# Automaton_no_switches.net
KiCad netlist of a schematic drawn in EAGLE
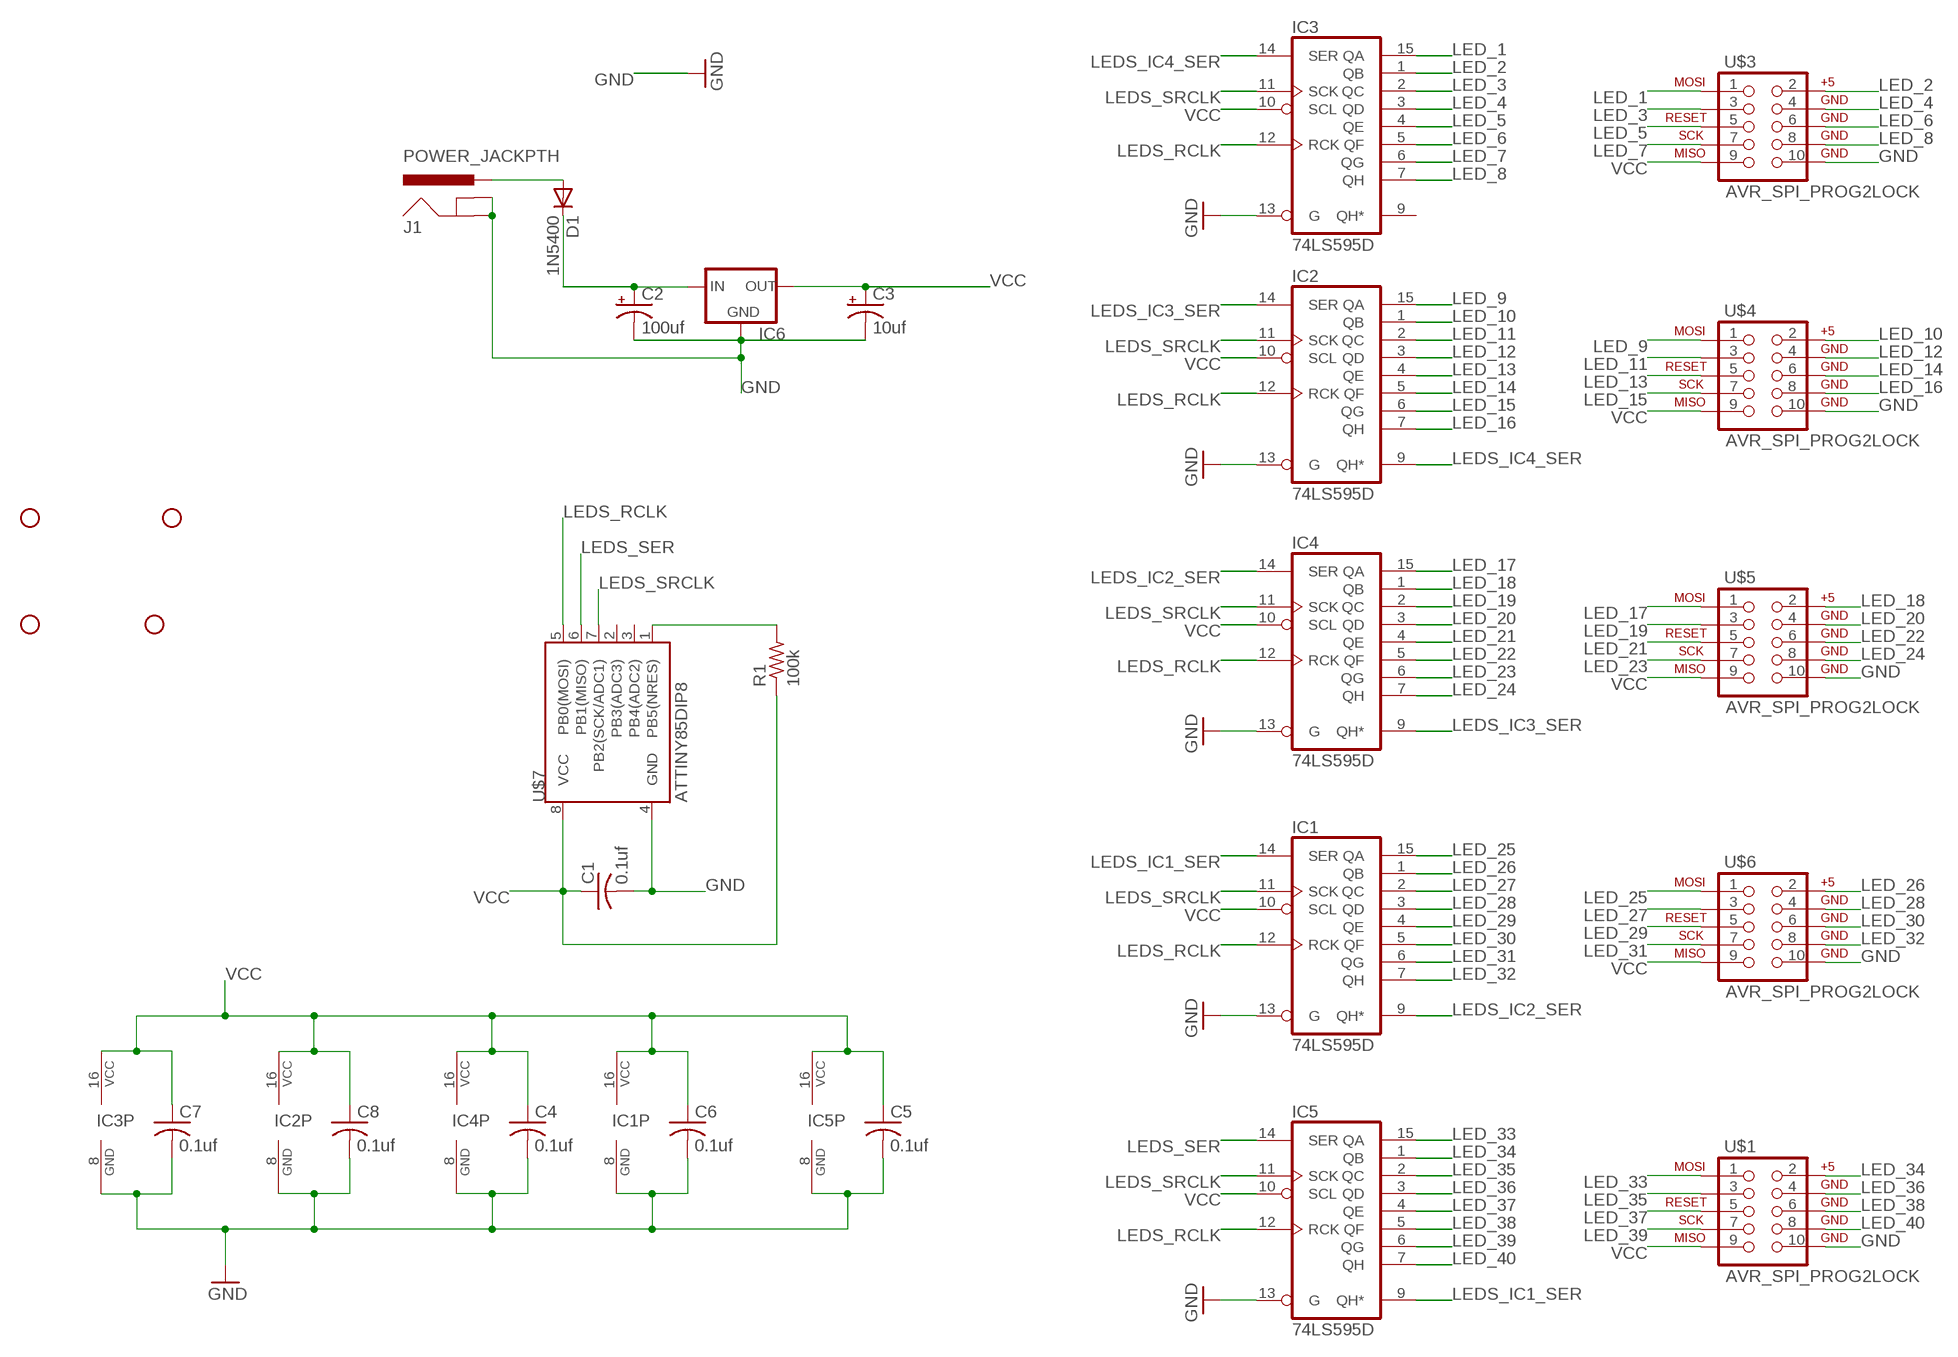
[diagram p0: schematic, sheet 1]

(export (version "E")
  (design (tool "Eeschema 10.0.6"))
  (components
    (comp (ref "C1")
      (value "0.1uf")
      (footprint "eagle-import:C1206")
      (libsource (lib "eagle-import") (part "C-USC1206"))
    )
    (comp (ref "C2")
      (value "100uf")
      (footprint "eagle-import:E5-10,5")
      (libsource (lib "eagle-import") (part "CPOL-USE5-10.5"))
    )
    (comp (ref "C3")
      (value "10uf")
      (footprint "eagle-import:E2-5")
      (libsource (lib "eagle-import") (part "CPOL-USE2-5"))
    )
    (comp (ref "C4")
      (value "0.1uf")
      (footprint "eagle-import:C1206")
      (libsource (lib "eagle-import") (part "C-USC1206"))
    )
    (comp (ref "C5")
      (value "0.1uf")
      (footprint "eagle-import:C1206")
      (libsource (lib "eagle-import") (part "C-USC1206"))
    )
    (comp (ref "C6")
      (value "0.1uf")
      (footprint "eagle-import:C1206")
      (libsource (lib "eagle-import") (part "C-USC1206"))
    )
    (comp (ref "C7")
      (value "0.1uf")
      (footprint "eagle-import:C1206")
      (libsource (lib "eagle-import") (part "C-USC1206"))
    )
    (comp (ref "C8")
      (value "0.1uf")
      (footprint "eagle-import:C1206")
      (libsource (lib "eagle-import") (part "C-USC1206"))
    )
    (comp (ref "D1")
      (value "1N5400")
      (footprint "eagle-import:DO201-15")
      (libsource (lib "eagle-import") (part "1N5400"))
    )
    (comp (ref "IC1")
      (value "74LS595D")
      (footprint "eagle-import:SO16")
      (libsource (lib "eagle-import") (part "74595DLS"))
    )
    (comp (ref "IC2")
      (value "74LS595D")
      (footprint "eagle-import:SO16")
      (libsource (lib "eagle-import") (part "74595DLS"))
    )
    (comp (ref "IC3")
      (value "74LS595D")
      (footprint "eagle-import:SO16")
      (libsource (lib "eagle-import") (part "74595DLS"))
    )
    (comp (ref "IC4")
      (value "74LS595D")
      (footprint "eagle-import:SO16")
      (libsource (lib "eagle-import") (part "74595DLS"))
    )
    (comp (ref "IC5")
      (value "74LS595D")
      (footprint "eagle-import:SO16")
      (libsource (lib "eagle-import") (part "74595DLS"))
    )
    (comp (ref "IC6")
      (value "V_REG_78XXSINK")
      (footprint "eagle-import:TO220-IGO")
      (libsource (lib "eagle-import") (part "V_REG_78XXSINK"))
    )
    (comp (ref "J1")
      (value "POWER_JACKPTH")
      (footprint "eagle-import:POWER_JACK_PTH")
      (libsource (lib "eagle-import") (part "POWER_JACKPTH"))
    )
    (comp (ref "JP1")
      (value "STAND-OFF")
      (footprint "eagle-import:STAND-OFF")
      (libsource (lib "eagle-import") (part "STAND-OFF"))
    )
    (comp (ref "JP2")
      (value "STAND-OFF")
      (footprint "eagle-import:STAND-OFF")
      (libsource (lib "eagle-import") (part "STAND-OFF"))
    )
    (comp (ref "JP3")
      (value "STAND-OFF")
      (footprint "eagle-import:STAND-OFF")
      (libsource (lib "eagle-import") (part "STAND-OFF"))
    )
    (comp (ref "JP4")
      (value "STAND-OFF")
      (footprint "eagle-import:STAND-OFF")
      (libsource (lib "eagle-import") (part "STAND-OFF"))
    )
    (comp (ref "R1")
      (value "100k")
      (footprint "eagle-import:M1206")
      (libsource (lib "eagle-import") (part "R-US_M1206"))
    )
    (comp (ref "U$1")
      (value "AVR_SPI_PROG2LOCK")
      (footprint "eagle-import:2X5-SHROUDED_LOCK")
      (libsource (lib "eagle-import") (part "AVR_SPI_PROG2LOCK"))
    )
    (comp (ref "U$3")
      (value "AVR_SPI_PROG2LOCK")
      (footprint "eagle-import:2X5-SHROUDED_LOCK")
      (libsource (lib "eagle-import") (part "AVR_SPI_PROG2LOCK"))
    )
    (comp (ref "U$4")
      (value "AVR_SPI_PROG2LOCK")
      (footprint "eagle-import:2X5-SHROUDED_LOCK")
      (libsource (lib "eagle-import") (part "AVR_SPI_PROG2LOCK"))
    )
    (comp (ref "U$5")
      (value "AVR_SPI_PROG2LOCK")
      (footprint "eagle-import:2X5-SHROUDED_LOCK")
      (libsource (lib "eagle-import") (part "AVR_SPI_PROG2LOCK"))
    )
    (comp (ref "U$6")
      (value "AVR_SPI_PROG2LOCK")
      (footprint "eagle-import:2X5-SHROUDED_LOCK")
      (libsource (lib "eagle-import") (part "AVR_SPI_PROG2LOCK"))
    )
    (comp (ref "U$7")
      (value "ATTINY85DIP8")
      (footprint "eagle-import:DIP08")
      (libsource (lib "eagle-import") (part "ATTINY85DIP8"))
    )
  )
  (nets
    (net (code "1") (name "/LEDS_IC1_SER") (class "Default")
      (node (ref "IC1") (pin "14") (pinfunction "SER_14") (pintype "input"))
      (node (ref "IC5") (pin "9") (pinfunction "QH*_9") (pintype "tri_state"))
    )
    (net (code "2") (name "/LEDS_IC2_SER") (class "Default")
      (node (ref "IC1") (pin "9") (pinfunction "QH*_9") (pintype "tri_state"))
      (node (ref "IC4") (pin "14") (pinfunction "SER_14") (pintype "input"))
    )
    (net (code "3") (name "/LEDS_IC3_SER") (class "Default")
      (node (ref "IC2") (pin "14") (pinfunction "SER_14") (pintype "input"))
      (node (ref "IC4") (pin "9") (pinfunction "QH*_9") (pintype "tri_state"))
    )
    (net (code "4") (name "/LEDS_IC4_SER") (class "Default")
      (node (ref "IC2") (pin "9") (pinfunction "QH*_9") (pintype "tri_state"))
      (node (ref "IC3") (pin "14") (pinfunction "SER_14") (pintype "input"))
    )
    (net (code "5") (name "/LEDS_RCLK") (class "Default")
      (node (ref "IC1") (pin "12") (pinfunction "RCK_12") (pintype "input"))
      (node (ref "IC2") (pin "12") (pinfunction "RCK_12") (pintype "input"))
      (node (ref "IC3") (pin "12") (pinfunction "RCK_12") (pintype "input"))
      (node (ref "IC4") (pin "12") (pinfunction "RCK_12") (pintype "input"))
      (node (ref "IC5") (pin "12") (pinfunction "RCK_12") (pintype "input"))
      (node (ref "U$7") (pin "5") (pinfunction "PB0(MOSI)_5") (pintype "bidirectional"))
    )
    (net (code "6") (name "/LEDS_SER") (class "Default")
      (node (ref "IC5") (pin "14") (pinfunction "SER_14") (pintype "input"))
      (node (ref "U$7") (pin "6") (pinfunction "PB1(MISO)_6") (pintype "bidirectional"))
    )
    (net (code "7") (name "/LEDS_SRCLK") (class "Default")
      (node (ref "IC1") (pin "11") (pinfunction "SCK_11") (pintype "input"))
      (node (ref "IC2") (pin "11") (pinfunction "SCK_11") (pintype "input"))
      (node (ref "IC3") (pin "11") (pinfunction "SCK_11") (pintype "input"))
      (node (ref "IC4") (pin "11") (pinfunction "SCK_11") (pintype "input"))
      (node (ref "IC5") (pin "11") (pinfunction "SCK_11") (pintype "input"))
      (node (ref "U$7") (pin "7") (pinfunction "PB2(SCK/ADC1)_7") (pintype "bidirectional"))
    )
    (net (code "8") (name "/LED_1") (class "Default")
      (node (ref "IC3") (pin "15") (pinfunction "QA_15") (pintype "tri_state"))
      (node (ref "U$3") (pin "1") (pinfunction "1_1") (pintype "passive"))
    )
    (net (code "9") (name "/LED_2") (class "Default")
      (node (ref "IC3") (pin "1") (pinfunction "QB_1") (pintype "tri_state"))
      (node (ref "U$3") (pin "2") (pinfunction "2_2") (pintype "passive"))
    )
    (net (code "10") (name "/LED_3") (class "Default")
      (node (ref "IC3") (pin "2") (pinfunction "QC_2") (pintype "tri_state"))
      (node (ref "U$3") (pin "3") (pinfunction "3_3") (pintype "passive"))
    )
    (net (code "11") (name "/LED_4") (class "Default")
      (node (ref "IC3") (pin "3") (pinfunction "QD_3") (pintype "tri_state"))
      (node (ref "U$3") (pin "4") (pinfunction "4_4") (pintype "passive"))
    )
    (net (code "12") (name "/LED_5") (class "Default")
      (node (ref "IC3") (pin "4") (pinfunction "QE_4") (pintype "tri_state"))
      (node (ref "U$3") (pin "5") (pinfunction "5_5") (pintype "passive"))
    )
    (net (code "13") (name "/LED_6") (class "Default")
      (node (ref "IC3") (pin "5") (pinfunction "QF_5") (pintype "tri_state"))
      (node (ref "U$3") (pin "6") (pinfunction "6_6") (pintype "passive"))
    )
    (net (code "14") (name "/LED_7") (class "Default")
      (node (ref "IC3") (pin "6") (pinfunction "QG_6") (pintype "tri_state"))
      (node (ref "U$3") (pin "7") (pinfunction "7_7") (pintype "passive"))
    )
    (net (code "15") (name "/LED_8") (class "Default")
      (node (ref "IC3") (pin "7") (pinfunction "QH_7") (pintype "tri_state"))
      (node (ref "U$3") (pin "8") (pinfunction "8_8") (pintype "passive"))
    )
    (net (code "16") (name "/LED_9") (class "Default")
      (node (ref "IC2") (pin "15") (pinfunction "QA_15") (pintype "tri_state"))
      (node (ref "U$4") (pin "1") (pinfunction "1_1") (pintype "passive"))
    )
    (net (code "17") (name "/LED_10") (class "Default")
      (node (ref "IC2") (pin "1") (pinfunction "QB_1") (pintype "tri_state"))
      (node (ref "U$4") (pin "2") (pinfunction "2_2") (pintype "passive"))
    )
    (net (code "18") (name "/LED_11") (class "Default")
      (node (ref "IC2") (pin "2") (pinfunction "QC_2") (pintype "tri_state"))
      (node (ref "U$4") (pin "3") (pinfunction "3_3") (pintype "passive"))
    )
    (net (code "19") (name "/LED_12") (class "Default")
      (node (ref "IC2") (pin "3") (pinfunction "QD_3") (pintype "tri_state"))
      (node (ref "U$4") (pin "4") (pinfunction "4_4") (pintype "passive"))
    )
    (net (code "20") (name "/LED_13") (class "Default")
      (node (ref "IC2") (pin "4") (pinfunction "QE_4") (pintype "tri_state"))
      (node (ref "U$4") (pin "5") (pinfunction "5_5") (pintype "passive"))
    )
    (net (code "21") (name "/LED_14") (class "Default")
      (node (ref "IC2") (pin "5") (pinfunction "QF_5") (pintype "tri_state"))
      (node (ref "U$4") (pin "6") (pinfunction "6_6") (pintype "passive"))
    )
    (net (code "22") (name "/LED_15") (class "Default")
      (node (ref "IC2") (pin "6") (pinfunction "QG_6") (pintype "tri_state"))
      (node (ref "U$4") (pin "7") (pinfunction "7_7") (pintype "passive"))
    )
    (net (code "23") (name "/LED_16") (class "Default")
      (node (ref "IC2") (pin "7") (pinfunction "QH_7") (pintype "tri_state"))
      (node (ref "U$4") (pin "8") (pinfunction "8_8") (pintype "passive"))
    )
    (net (code "24") (name "/LED_17") (class "Default")
      (node (ref "IC4") (pin "15") (pinfunction "QA_15") (pintype "tri_state"))
      (node (ref "U$5") (pin "1") (pinfunction "1_1") (pintype "passive"))
    )
    (net (code "25") (name "/LED_18") (class "Default")
      (node (ref "IC4") (pin "1") (pinfunction "QB_1") (pintype "tri_state"))
      (node (ref "U$5") (pin "2") (pinfunction "2_2") (pintype "passive"))
    )
    (net (code "26") (name "/LED_19") (class "Default")
      (node (ref "IC4") (pin "2") (pinfunction "QC_2") (pintype "tri_state"))
      (node (ref "U$5") (pin "3") (pinfunction "3_3") (pintype "passive"))
    )
    (net (code "27") (name "/LED_20") (class "Default")
      (node (ref "IC4") (pin "3") (pinfunction "QD_3") (pintype "tri_state"))
      (node (ref "U$5") (pin "4") (pinfunction "4_4") (pintype "passive"))
    )
    (net (code "28") (name "/LED_21") (class "Default")
      (node (ref "IC4") (pin "4") (pinfunction "QE_4") (pintype "tri_state"))
      (node (ref "U$5") (pin "5") (pinfunction "5_5") (pintype "passive"))
    )
    (net (code "29") (name "/LED_22") (class "Default")
      (node (ref "IC4") (pin "5") (pinfunction "QF_5") (pintype "tri_state"))
      (node (ref "U$5") (pin "6") (pinfunction "6_6") (pintype "passive"))
    )
    (net (code "30") (name "/LED_23") (class "Default")
      (node (ref "IC4") (pin "6") (pinfunction "QG_6") (pintype "tri_state"))
      (node (ref "U$5") (pin "7") (pinfunction "7_7") (pintype "passive"))
    )
    (net (code "31") (name "/LED_24") (class "Default")
      (node (ref "IC4") (pin "7") (pinfunction "QH_7") (pintype "tri_state"))
      (node (ref "U$5") (pin "8") (pinfunction "8_8") (pintype "passive"))
    )
    (net (code "32") (name "/LED_25") (class "Default")
      (node (ref "IC1") (pin "15") (pinfunction "QA_15") (pintype "tri_state"))
      (node (ref "U$6") (pin "1") (pinfunction "1_1") (pintype "passive"))
    )
    (net (code "33") (name "/LED_26") (class "Default")
      (node (ref "IC1") (pin "1") (pinfunction "QB_1") (pintype "tri_state"))
      (node (ref "U$6") (pin "2") (pinfunction "2_2") (pintype "passive"))
    )
    (net (code "34") (name "/LED_27") (class "Default")
      (node (ref "IC1") (pin "2") (pinfunction "QC_2") (pintype "tri_state"))
      (node (ref "U$6") (pin "3") (pinfunction "3_3") (pintype "passive"))
    )
    (net (code "35") (name "/LED_28") (class "Default")
      (node (ref "IC1") (pin "3") (pinfunction "QD_3") (pintype "tri_state"))
      (node (ref "U$6") (pin "4") (pinfunction "4_4") (pintype "passive"))
    )
    (net (code "36") (name "/LED_29") (class "Default")
      (node (ref "IC1") (pin "4") (pinfunction "QE_4") (pintype "tri_state"))
      (node (ref "U$6") (pin "5") (pinfunction "5_5") (pintype "passive"))
    )
    (net (code "37") (name "/LED_30") (class "Default")
      (node (ref "IC1") (pin "5") (pinfunction "QF_5") (pintype "tri_state"))
      (node (ref "U$6") (pin "6") (pinfunction "6_6") (pintype "passive"))
    )
    (net (code "38") (name "/LED_31") (class "Default")
      (node (ref "IC1") (pin "6") (pinfunction "QG_6") (pintype "tri_state"))
      (node (ref "U$6") (pin "7") (pinfunction "7_7") (pintype "passive"))
    )
    (net (code "39") (name "/LED_32") (class "Default")
      (node (ref "IC1") (pin "7") (pinfunction "QH_7") (pintype "tri_state"))
      (node (ref "U$6") (pin "8") (pinfunction "8_8") (pintype "passive"))
    )
    (net (code "40") (name "/LED_33") (class "Default")
      (node (ref "IC5") (pin "15") (pinfunction "QA_15") (pintype "tri_state"))
      (node (ref "U$1") (pin "1") (pinfunction "1_1") (pintype "passive"))
    )
    (net (code "41") (name "/LED_34") (class "Default")
      (node (ref "IC5") (pin "1") (pinfunction "QB_1") (pintype "tri_state"))
      (node (ref "U$1") (pin "2") (pinfunction "2_2") (pintype "passive"))
    )
    (net (code "42") (name "/LED_35") (class "Default")
      (node (ref "IC5") (pin "2") (pinfunction "QC_2") (pintype "tri_state"))
      (node (ref "U$1") (pin "3") (pinfunction "3_3") (pintype "passive"))
    )
    (net (code "43") (name "/LED_36") (class "Default")
      (node (ref "IC5") (pin "3") (pinfunction "QD_3") (pintype "tri_state"))
      (node (ref "U$1") (pin "4") (pinfunction "4_4") (pintype "passive"))
    )
    (net (code "44") (name "/LED_37") (class "Default")
      (node (ref "IC5") (pin "4") (pinfunction "QE_4") (pintype "tri_state"))
      (node (ref "U$1") (pin "5") (pinfunction "5_5") (pintype "passive"))
    )
    (net (code "45") (name "/LED_38") (class "Default")
      (node (ref "IC5") (pin "5") (pinfunction "QF_5") (pintype "tri_state"))
      (node (ref "U$1") (pin "6") (pinfunction "6_6") (pintype "passive"))
    )
    (net (code "46") (name "/LED_39") (class "Default")
      (node (ref "IC5") (pin "6") (pinfunction "QG_6") (pintype "tri_state"))
      (node (ref "U$1") (pin "7") (pinfunction "7_7") (pintype "passive"))
    )
    (net (code "47") (name "/LED_40") (class "Default")
      (node (ref "IC5") (pin "7") (pinfunction "QH_7") (pintype "tri_state"))
      (node (ref "U$1") (pin "8") (pinfunction "8_8") (pintype "passive"))
    )
    (net (code "48") (name "/VCC") (class "Default")
      (node (ref "C1") (pin "1") (pinfunction "1_1") (pintype "passive"))
      (node (ref "C3") (pin "+") (pinfunction "+_+") (pintype "passive"))
      (node (ref "C4") (pin "1") (pinfunction "1_1") (pintype "passive"))
      (node (ref "C5") (pin "1") (pinfunction "1_1") (pintype "passive"))
      (node (ref "C6") (pin "1") (pinfunction "1_1") (pintype "passive"))
      (node (ref "C7") (pin "1") (pinfunction "1_1") (pintype "passive"))
      (node (ref "C8") (pin "1") (pinfunction "1_1") (pintype "passive"))
      (node (ref "IC1") (pin "10") (pinfunction "SCL_10") (pintype "input"))
      (node (ref "IC1") (pin "16") (pinfunction "VCC_16") (pintype "power_in"))
      (node (ref "IC2") (pin "10") (pinfunction "SCL_10") (pintype "input"))
      (node (ref "IC2") (pin "16") (pinfunction "VCC_16") (pintype "power_in"))
      (node (ref "IC3") (pin "10") (pinfunction "SCL_10") (pintype "input"))
      (node (ref "IC3") (pin "16") (pinfunction "VCC_16") (pintype "power_in"))
      (node (ref "IC4") (pin "10") (pinfunction "SCL_10") (pintype "input"))
      (node (ref "IC4") (pin "16") (pinfunction "VCC_16") (pintype "power_in"))
      (node (ref "IC5") (pin "10") (pinfunction "SCL_10") (pintype "input"))
      (node (ref "IC5") (pin "16") (pinfunction "VCC_16") (pintype "power_in"))
      (node (ref "IC6") (pin "OUT") (pinfunction "OUT_OUT") (pintype "output"))
      (node (ref "R1") (pin "1") (pinfunction "1_1") (pintype "passive"))
      (node (ref "U$1") (pin "9") (pinfunction "9_9") (pintype "passive"))
      (node (ref "U$3") (pin "9") (pinfunction "9_9") (pintype "passive"))
      (node (ref "U$4") (pin "9") (pinfunction "9_9") (pintype "passive"))
      (node (ref "U$5") (pin "9") (pinfunction "9_9") (pintype "passive"))
      (node (ref "U$6") (pin "9") (pinfunction "9_9") (pintype "passive"))
      (node (ref "U$7") (pin "8") (pinfunction "VCC_8") (pintype "bidirectional"))
    )
    (net (code "49") (name "GND") (class "Default")
      (node (ref "C1") (pin "2") (pinfunction "2_2") (pintype "passive"))
      (node (ref "C2") (pin "-") (pinfunction "-_-") (pintype "passive"))
      (node (ref "C3") (pin "-") (pinfunction "-_-") (pintype "passive"))
      (node (ref "C4") (pin "2") (pinfunction "2_2") (pintype "passive"))
      (node (ref "C5") (pin "2") (pinfunction "2_2") (pintype "passive"))
      (node (ref "C6") (pin "2") (pinfunction "2_2") (pintype "passive"))
      (node (ref "C7") (pin "2") (pinfunction "2_2") (pintype "passive"))
      (node (ref "C8") (pin "2") (pinfunction "2_2") (pintype "passive"))
      (node (ref "IC1") (pin "13") (pinfunction "G_13") (pintype "input"))
      (node (ref "IC1") (pin "8") (pinfunction "GND_8") (pintype "power_in"))
      (node (ref "IC2") (pin "13") (pinfunction "G_13") (pintype "input"))
      (node (ref "IC2") (pin "8") (pinfunction "GND_8") (pintype "power_in"))
      (node (ref "IC3") (pin "13") (pinfunction "G_13") (pintype "input"))
      (node (ref "IC3") (pin "8") (pinfunction "GND_8") (pintype "power_in"))
      (node (ref "IC4") (pin "13") (pinfunction "G_13") (pintype "input"))
      (node (ref "IC4") (pin "8") (pinfunction "GND_8") (pintype "power_in"))
      (node (ref "IC5") (pin "13") (pinfunction "G_13") (pintype "input"))
      (node (ref "IC5") (pin "8") (pinfunction "GND_8") (pintype "power_in"))
      (node (ref "IC6") (pin "GND") (pinfunction "GND_GND") (pintype "input"))
      (node (ref "J1") (pin "GND") (pinfunction "GND_GND") (pintype "bidirectional"))
      (node (ref "J1") (pin "GNDBREAK") (pinfunction "GNDBREAK_GNDBREAK") (pintype "bidirectional"))
      (node (ref "U$1") (pin "10") (pinfunction "10_10") (pintype "passive"))
      (node (ref "U$3") (pin "10") (pinfunction "10_10") (pintype "passive"))
      (node (ref "U$4") (pin "10") (pinfunction "10_10") (pintype "passive"))
      (node (ref "U$5") (pin "10") (pinfunction "10_10") (pintype "passive"))
      (node (ref "U$6") (pin "10") (pinfunction "10_10") (pintype "passive"))
      (node (ref "U$7") (pin "4") (pinfunction "GND_4") (pintype "bidirectional"))
    )
    (net (code "50") (name "Net-(C2-Pad+)") (class "Default")
      (node (ref "C2") (pin "+") (pinfunction "+_+") (pintype "passive"))
      (node (ref "D1") (pin "C") (pinfunction "C_C") (pintype "passive"))
      (node (ref "IC6") (pin "IN") (pinfunction "IN_IN") (pintype "input"))
    )
    (net (code "51") (name "Net-(D1-PadA)") (class "Default")
      (node (ref "D1") (pin "A") (pinfunction "A_A") (pintype "passive"))
      (node (ref "J1") (pin "PWR") (pinfunction "PWR_PWR") (pintype "bidirectional"))
    )
    (net (code "52") (name "Net-(U$7-PB5(NRES))") (class "Default")
      (node (ref "R1") (pin "2") (pinfunction "2_2") (pintype "passive"))
      (node (ref "U$7") (pin "1") (pinfunction "PB5(NRES)_1") (pintype "bidirectional"))
    )
    (net (code "53") (name "unconnected-(IC3A-QH*-Pad9)") (class "Default")
      (node (ref "IC3") (pin "9") (pinfunction "QH*_9") (pintype "tri_state"))
    )
    (net (code "54") (name "unconnected-(U$7-PB3(ADC3)-Pad2)") (class "Default")
      (node (ref "U$7") (pin "2") (pinfunction "PB3(ADC3)_2") (pintype "bidirectional"))
    )
    (net (code "55") (name "unconnected-(U$7-PB4(ADC2)-Pad3)") (class "Default")
      (node (ref "U$7") (pin "3") (pinfunction "PB4(ADC2)_3") (pintype "bidirectional"))
    )
  )
)
